# power.net
KiCad netlist of a schematic drawn in Altium Designer
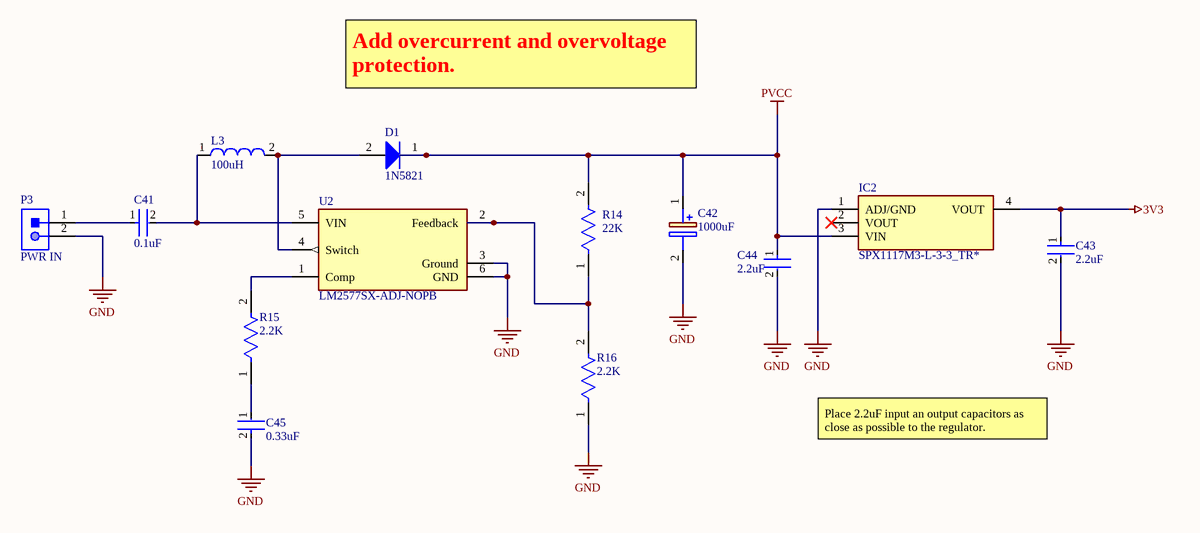
[diagram p0: power.SchDoc]

(export (version "E")
  (design (tool "Eeschema 10.0.6"))
  (components
    (comp (ref "C41")
      (value "0.1uF")
      (footprint "TDK_C2012-125-0_2_IPC_A")
      (description "C Series 0805 0.1 uF 100 V ±10 % Tolerance X7R SMT Multilayer Ceramic Capacitor")
      (fields (field (name "MANUFACTURER") "TDK") (field (name "MANUFACTURER PART NUMBER") "C2012X7R2A104K"))
      (libsource (lib "project_x_sch_library") (part "C2012X7R2A104K125AA"))
    )
    (comp (ref "C42")
      (value "1000uF")
      (footprint "CAPPRD500W60D1275H2700")
      (description "CAP ALUM 1000UF 20% 50V RADIAL")
      (fields
        (field (name "MANUFACTURER_PART_NUMBER") "UVR1H102MHD1TO")
        (field (name "MOUSER PART NUMBER") "647-UVR1H102MHD1T0")
      )
      (libsource (lib "project_x_sch_library") (part "UVR1H102MHD1TO"))
    )
    (comp (ref "C43")
      (value "2.2uF")
      (footprint "Samsung_CL21_IPC_A")
      (description "CAP CER 2.2UF 25V X7R 0805")
      (fields
        (field (name "MANUFACTURER") "Samsung")
        (field (name "MANUFACTURER PART NUMBER") "CL21B225KAFNFNE")
      )
      (libsource (lib "project_x_sch_library") (part "CL21B225KAFNFNE"))
    )
    (comp (ref "C44")
      (value "2.2uF")
      (footprint "Samsung_CL21_IPC_A")
      (description "CAP CER 2.2UF 25V X7R 0805")
      (fields
        (field (name "MANUFACTURER") "Samsung")
        (field (name "MANUFACTURER PART NUMBER") "CL21B225KAFNFNE")
      )
      (libsource (lib "project_x_sch_library") (part "CL21B225KAFNFNE"))
    )
    (comp (ref "C45")
      (value "0.33uF")
      (footprint "TDK_C1608-080-0_1_IPC_B")
      (description "Cap Ceramic 0.33uF 50V X7R 10% Pad SMD 0603 125°C Low ESR T/R")
      (fields
        (field (name "MANUFACTURER") "TDK")
        (field (name "MANUFACTURER PART NUMBER") "C1608X7R1H334K080AC")
      )
      (libsource (lib "project_x_sch_library") (part "C1608X7R1H334K080AC"))
    )
    (comp (ref "D1")
      (value "1N5821")
      (footprint "ONSC-AXIAL_LEAD-2-267-05_V")
      (description "Diode Schottky 30V 3A Through Hole DO-201AD")
      (fields (field (name "MANUFACTURER") "On Semiconductor"))
      (libsource (lib "project_x_sch_library") (part "1N5821"))
    )
    (comp (ref "IC2")
      (value "SPX1117M3-L-3-3_TR*")
      (footprint "SOT230P700X180-4N")
      (description "IC REG LINEAR 3.3V 800MA SOT223 LDO")
      (fields
        (field (name "MANUFACTURER_PART_NUMBER") "SPX1117M3-L-3-3/TR")
        (field (name "MOUSER PART NUMBER") "701-SPX1117M3-L-33TR")
      )
      (libsource (lib "project_x_sch_library") (part "SPX1117M3-L-3-3_TR"))
    )
    (comp (ref "L3")
      (value "100uH")
      (footprint "WE-PD-XXL")
      (fields
        (field (name "PARTNUMBER") "7447709101")
        (field (name "MANUFACTURER") "Wurth Electronics")
        (field (name "TOLERANCE") "20%")
      )
      (libsource (lib "project_x_sch_library") (part "7447709101"))
    )
    (comp (ref "P3")
      (value "PWR IN")
      (footprint "PHOE-1803277_V")
      (description "Conn;  TermBlk;  PCB;  Header;  SnglLvl;  90DegAngl;  Sldr;  2Pole;  3.81mmPitch;  COMBICON")
      (fields (field (name "TOLERANCE") "5%") (field (name "PARTNUMBER") "1803277"))
      (libsource (lib "project_x_sch_library") (part "1803277"))
    )
    (comp (ref "R14")
      (value "22K")
      (footprint "TE_Connectivity_CRGCQ2512_IPC_A")
      (fields
        (field (name "MANUFACTURER") "TE Connectivity")
        (field (name "MANUFACTURER PART NUMBER") "CRGCQ2512F22K")
      )
      (libsource (lib "project_x_sch_library") (part "CRGCQ2512F22K"))
    )
    (comp (ref "R15")
      (value "2.2K")
      (footprint "KOA_Speer_RK73H2E_IPC_A")
      (description "Thick Film Resistors 1/2watts 2.2Kohms 1%")
      (fields
        (field (name "MANUFACTURER") "KOA Speer")
        (field (name "MANUFACTURER PART NUMBER") "RK73H2ETTD2201F")
      )
      (libsource (lib "project_x_sch_library") (part "RK73H2ETTD2201F"))
    )
    (comp (ref "R16")
      (value "2.2K")
      (footprint "KOA_Speer_RK73H2E_IPC_A")
      (description "Thick Film Resistors 1/2watts 2.2Kohms 1%")
      (fields
        (field (name "MANUFACTURER") "KOA Speer")
        (field (name "MANUFACTURER PART NUMBER") "RK73H2ETTD2201F")
      )
      (libsource (lib "project_x_sch_library") (part "RK73H2ETTD2201F"))
    )
    (comp (ref "U2")
      (value "LM2577SX-ADJ-NOPB")
      (footprint "Texas_Instruments_KTT0005B_MFG")
      (description "Conv DC-DC 3.5V to 40V Step Up Single-Out 11.6V to 12.4V 3A 6-Pin(5+Tab) TO-263 T/R")
      (fields
        (field (name "MANUFACTURER") "TI National Semiconductor")
        (field (name "MANUFACTURER PART NUMBER") "LM2577SX-ADJ/NOPB")
      )
      (libsource (lib "project_x_sch_library") (part "LM2577SX-ADJ-NOPB"))
    )
  )
  (nets
    (net (code "1") (name "3V3") (class "Default")
      (node (ref "C43") (pin "1") (pinfunction "1_1") (pintype "passive"))
      (node (ref "IC2") (pin "4") (pinfunction "VOUT_4") (pintype "passive"))
    )
    (net (code "2") (name "GND") (class "Default")
      (node (ref "C42") (pin "2") (pinfunction "-_2") (pintype "passive"))
      (node (ref "C43") (pin "2") (pinfunction "2_2") (pintype "passive"))
      (node (ref "C44") (pin "2") (pinfunction "2_2") (pintype "passive"))
      (node (ref "C45") (pin "2") (pinfunction "2_2") (pintype "passive"))
      (node (ref "IC2") (pin "1") (pinfunction "ADJ/GND_1") (pintype "passive"))
      (node (ref "P3") (pin "2") (pinfunction "2_2") (pintype "passive"))
      (node (ref "R16") (pin "1") (pinfunction "1_1") (pintype "passive"))
      (node (ref "U2") (pin "3") (pinfunction "Ground_3") (pintype "power_in"))
      (node (ref "U2") (pin "6") (pinfunction "GND_6") (pintype "power_in"))
    )
    (net (code "3") (name "Net-(C41-Pad1)") (class "Default")
      (node (ref "C41") (pin "1") (pinfunction "1_1") (pintype "passive"))
      (node (ref "P3") (pin "1") (pinfunction "1_1") (pintype "passive"))
    )
    (net (code "4") (name "Net-(C45-Pad1)") (class "Default")
      (node (ref "C45") (pin "1") (pinfunction "1_1") (pintype "passive"))
      (node (ref "R15") (pin "1") (pinfunction "1_1") (pintype "passive"))
    )
    (net (code "5") (name "Net-(D1-A)") (class "Default")
      (node (ref "D1") (pin "2") (pinfunction "A_2") (pintype "passive"))
      (node (ref "L3") (pin "2") (pinfunction "2_2") (pintype "passive"))
      (node (ref "U2") (pin "4") (pinfunction "Switch_4") (pintype "output"))
    )
    (net (code "6") (name "Net-(U2-Comp)") (class "Default")
      (node (ref "R15") (pin "2") (pinfunction "2_2") (pintype "passive"))
      (node (ref "U2") (pin "1") (pinfunction "Comp_1") (pintype "passive"))
    )
    (net (code "7") (name "Net-(U2-Feedback)") (class "Default")
      (node (ref "R14") (pin "1") (pinfunction "1_1") (pintype "passive"))
      (node (ref "R16") (pin "2") (pinfunction "2_2") (pintype "passive"))
      (node (ref "U2") (pin "2") (pinfunction "Feedback_2") (pintype "passive"))
    )
    (net (code "8") (name "Net-(U2-VIN)") (class "Default")
      (node (ref "C41") (pin "2") (pinfunction "2_2") (pintype "passive"))
      (node (ref "L3") (pin "1") (pinfunction "1_1") (pintype "passive"))
      (node (ref "U2") (pin "5") (pinfunction "VIN_5") (pintype "power_in"))
    )
    (net (code "9") (name "PVCC") (class "Default")
      (node (ref "C42") (pin "1") (pinfunction "+_1") (pintype "passive"))
      (node (ref "C44") (pin "1") (pinfunction "1_1") (pintype "passive"))
      (node (ref "D1") (pin "1") (pinfunction "K_1") (pintype "passive"))
      (node (ref "IC2") (pin "3") (pinfunction "VIN_3") (pintype "passive"))
      (node (ref "R14") (pin "2") (pinfunction "2_2") (pintype "passive"))
    )
    (net (code "10") (name "unconnected-(IC2-VOUT-Pad2)") (class "Default")
      (node (ref "IC2") (pin "2") (pinfunction "VOUT_2") (pintype "passive+no_connect"))
    )
  )
)
